# SerialSignal.net
KiCad netlist of a schematic drawn in EAGLE
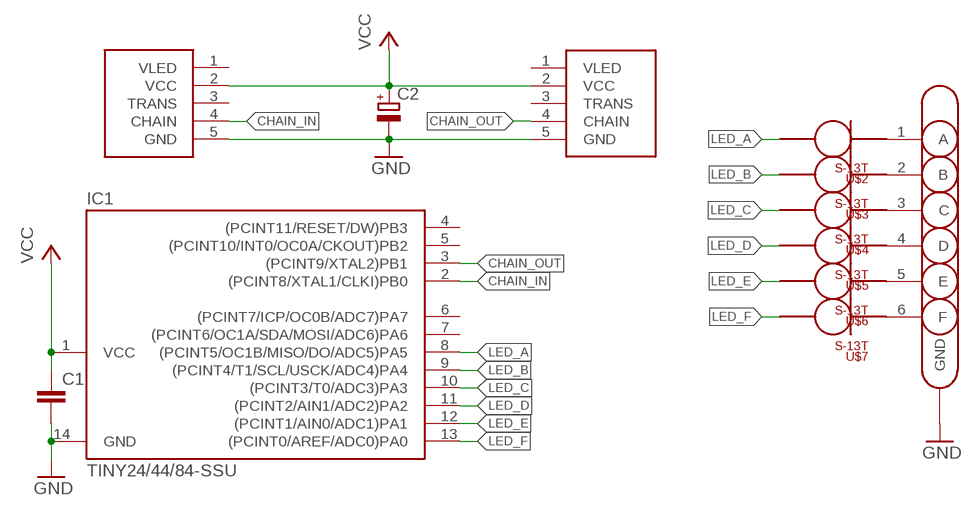
[diagram p0: schematic, sheet 1]

(export (version "E")
  (design (tool "Eeschema 10.0.6"))
  (components
    (comp (ref "C1")
      (value "C-EUC0603")
      (footprint "eagle-import:C0603")
      (libsource (lib "eagle-import") (part "C-EUC0603"))
    )
    (comp (ref "C2")
      (value "CPOL-EUSMCC")
      (footprint "eagle-import:SMC_C")
      (libsource (lib "eagle-import") (part "CPOL-EUSMCC"))
    )
    (comp (ref "IC1")
      (value "TINY24/44/84-SSU")
      (footprint "eagle-import:SOIC14")
      (libsource (lib "eagle-import") (part "TINY24/44/84-SSU"))
    )
    (comp (ref "SMD1")
      (value "SERIAL_SENSOR")
      (footprint "eagle-import:SERIAL_4")
      (libsource (lib "eagle-import") (part "SERIAL_SENSOR"))
    )
    (comp (ref "SMD2")
      (value "SERIAL_SENSOR")
      (footprint "eagle-import:SERIAL_4")
      (libsource (lib "eagle-import") (part "SERIAL_SENSOR"))
    )
    (comp (ref "U$1")
      (value "SIGNAL_CONNECTOR")
      (footprint "eagle-import:SIGNEL_CONNECTOR")
      (libsource (lib "eagle-import") (part "SIGNAL_CONNECTOR"))
    )
    (comp (ref "U$2")
      (value "S-13T")
      (footprint "eagle-import:S-1_3T")
      (libsource (lib "eagle-import") (part "S-13T"))
    )
    (comp (ref "U$3")
      (value "S-13T")
      (footprint "eagle-import:S-1_3T")
      (libsource (lib "eagle-import") (part "S-13T"))
    )
    (comp (ref "U$4")
      (value "S-13T")
      (footprint "eagle-import:S-1_3T")
      (libsource (lib "eagle-import") (part "S-13T"))
    )
    (comp (ref "U$5")
      (value "S-13T")
      (footprint "eagle-import:S-1_3T")
      (libsource (lib "eagle-import") (part "S-13T"))
    )
    (comp (ref "U$6")
      (value "S-13T")
      (footprint "eagle-import:S-1_3T")
      (libsource (lib "eagle-import") (part "S-13T"))
    )
    (comp (ref "U$7")
      (value "S-13T")
      (footprint "eagle-import:S-1_3T")
      (libsource (lib "eagle-import") (part "S-13T"))
    )
  )
  (nets
    (net (code "1") (name "CHAIN_IN") (class "Default")
      (node (ref "IC1") (pin "2") (pinfunction "(PCINT8/XTAL1/CLKI)PB0_2") (pintype "bidirectional"))
      (node (ref "SMD1") (pin "4") (pinfunction "CHAIN_4") (pintype "bidirectional"))
    )
    (net (code "2") (name "CHAIN_OUT") (class "Default")
      (node (ref "IC1") (pin "3") (pinfunction "(PCINT9/XTAL2)PB1_3") (pintype "bidirectional"))
      (node (ref "SMD2") (pin "4") (pinfunction "CHAIN_4") (pintype "bidirectional"))
    )
    (net (code "3") (name "GND") (class "Default")
      (node (ref "C1") (pin "2") (pinfunction "2_2") (pintype "passive"))
      (node (ref "C2") (pin "-") (pinfunction "-_-") (pintype "passive"))
      (node (ref "IC1") (pin "14") (pinfunction "GND_14") (pintype "power_in"))
      (node (ref "SMD1") (pin "5") (pinfunction "GND_5") (pintype "bidirectional"))
      (node (ref "SMD2") (pin "5") (pinfunction "GND_5") (pintype "bidirectional"))
      (node (ref "U$1") (pin "GND") (pinfunction "GND_GND") (pintype "bidirectional"))
    )
    (net (code "4") (name "LED_A") (class "Default")
      (node (ref "IC1") (pin "8") (pinfunction "(PCINT5/OC1B/MISO/DO/ADC5)PA5_8") (pintype "bidirectional"))
      (node (ref "U$2") (pin "A") (pinfunction "A_A") (pintype "bidirectional"))
    )
    (net (code "5") (name "LED_B") (class "Default")
      (node (ref "IC1") (pin "9") (pinfunction "(PCINT4/T1/SCL/USCK/ADC4)PA4_9") (pintype "bidirectional"))
      (node (ref "U$3") (pin "A") (pinfunction "A_A") (pintype "bidirectional"))
    )
    (net (code "6") (name "LED_C") (class "Default")
      (node (ref "IC1") (pin "10") (pinfunction "(PCINT3/T0/ADC3)PA3_10") (pintype "bidirectional"))
      (node (ref "U$4") (pin "A") (pinfunction "A_A") (pintype "bidirectional"))
    )
    (net (code "7") (name "LED_D") (class "Default")
      (node (ref "IC1") (pin "11") (pinfunction "(PCINT2/AIN1/ADC2)PA2_11") (pintype "bidirectional"))
      (node (ref "U$5") (pin "A") (pinfunction "A_A") (pintype "bidirectional"))
    )
    (net (code "8") (name "LED_E") (class "Default")
      (node (ref "IC1") (pin "12") (pinfunction "(PCINT1/AIN0/ADC1)PA1_12") (pintype "bidirectional"))
      (node (ref "U$6") (pin "A") (pinfunction "A_A") (pintype "bidirectional"))
    )
    (net (code "9") (name "LED_F") (class "Default")
      (node (ref "IC1") (pin "13") (pinfunction "(PCINT0/AREF/ADC0)PA0_13") (pintype "bidirectional"))
      (node (ref "U$7") (pin "A") (pinfunction "A_A") (pintype "bidirectional"))
    )
    (net (code "10") (name "Net-(U$1-A)") (class "Default")
      (node (ref "U$1") (pin "1") (pinfunction "A_1") (pintype "bidirectional"))
      (node (ref "U$2") (pin "C") (pinfunction "C_C") (pintype "bidirectional"))
    )
    (net (code "11") (name "Net-(U$1-B)") (class "Default")
      (node (ref "U$1") (pin "2") (pinfunction "B_2") (pintype "bidirectional"))
      (node (ref "U$3") (pin "C") (pinfunction "C_C") (pintype "bidirectional"))
    )
    (net (code "12") (name "Net-(U$1-C)") (class "Default")
      (node (ref "U$1") (pin "3") (pinfunction "C_3") (pintype "bidirectional"))
      (node (ref "U$4") (pin "C") (pinfunction "C_C") (pintype "bidirectional"))
    )
    (net (code "13") (name "Net-(U$1-D)") (class "Default")
      (node (ref "U$1") (pin "4") (pinfunction "D_4") (pintype "bidirectional"))
      (node (ref "U$5") (pin "C") (pinfunction "C_C") (pintype "bidirectional"))
    )
    (net (code "14") (name "Net-(U$1-E)") (class "Default")
      (node (ref "U$1") (pin "5") (pinfunction "E_5") (pintype "bidirectional"))
      (node (ref "U$6") (pin "C") (pinfunction "C_C") (pintype "bidirectional"))
    )
    (net (code "15") (name "Net-(U$1-F)") (class "Default")
      (node (ref "U$1") (pin "6") (pinfunction "F_6") (pintype "bidirectional"))
      (node (ref "U$7") (pin "C") (pinfunction "C_C") (pintype "bidirectional"))
    )
    (net (code "16") (name "VCC") (class "Default")
      (node (ref "C1") (pin "1") (pinfunction "1_1") (pintype "passive"))
      (node (ref "C2") (pin "+") (pinfunction "+_+") (pintype "passive"))
      (node (ref "IC1") (pin "1") (pinfunction "VCC_1") (pintype "power_in"))
      (node (ref "SMD1") (pin "2") (pinfunction "VCC_2") (pintype "bidirectional"))
      (node (ref "SMD2") (pin "2") (pinfunction "VCC_2") (pintype "bidirectional"))
    )
    (net (code "17") (name "unconnected-(IC1-(PCINT6{slash}OC1A{slash}SDA{slash}MOSI{slash}ADC6)PA6-Pad7)") (class "Default")
      (node (ref "IC1") (pin "7") (pinfunction "(PCINT6/OC1A/SDA/MOSI/ADC6)PA6_7") (pintype "bidirectional"))
    )
    (net (code "18") (name "unconnected-(IC1-(PCINT7{slash}ICP{slash}OC0B{slash}ADC7)PA7-Pad6)") (class "Default")
      (node (ref "IC1") (pin "6") (pinfunction "(PCINT7/ICP/OC0B/ADC7)PA7_6") (pintype "bidirectional"))
    )
    (net (code "19") (name "unconnected-(IC1-(PCINT10{slash}INT0{slash}OC0A{slash}CKOUT)PB2-Pad5)") (class "Default")
      (node (ref "IC1") (pin "5") (pinfunction "(PCINT10/INT0/OC0A/CKOUT)PB2_5") (pintype "bidirectional"))
    )
    (net (code "20") (name "unconnected-(IC1-(PCINT11{slash}RESET{slash}DW)PB3-Pad4)") (class "Default")
      (node (ref "IC1") (pin "4") (pinfunction "(PCINT11/RESET/DW)PB3_4") (pintype "bidirectional"))
    )
    (net (code "21") (name "unconnected-(SMD1-TRANS-Pad3)") (class "Default")
      (node (ref "SMD1") (pin "3") (pinfunction "TRANS_3") (pintype "bidirectional"))
    )
    (net (code "22") (name "unconnected-(SMD1-VLED-Pad1)") (class "Default")
      (node (ref "SMD1") (pin "1") (pinfunction "VLED_1") (pintype "bidirectional"))
    )
    (net (code "23") (name "unconnected-(SMD2-TRANS-Pad3)") (class "Default")
      (node (ref "SMD2") (pin "3") (pinfunction "TRANS_3") (pintype "bidirectional"))
    )
    (net (code "24") (name "unconnected-(SMD2-VLED-Pad1)") (class "Default")
      (node (ref "SMD2") (pin "1") (pinfunction "VLED_1") (pintype "bidirectional"))
    )
  )
)
